# Add-OnV11.net
KiCad netlist of a schematic drawn in EAGLE
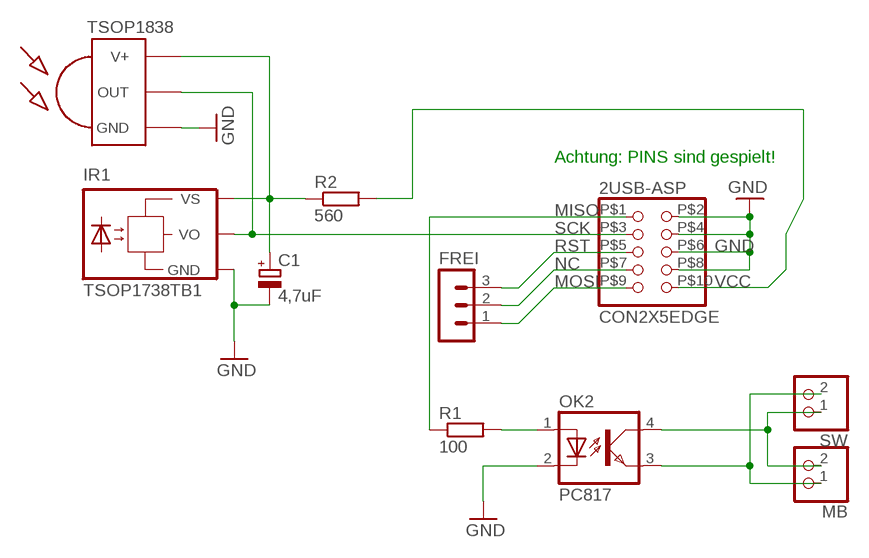
[diagram p0: schematic, sheet 1]

(export (version "E")
  (design (tool "Eeschema 10.0.6"))
  (components
    (comp (ref "2USB-ASP")
      (value "CON2X5EDGE")
      (footprint "eagle-import:CON2X5EDGE")
      (libsource (lib "eagle-import") (part "CON2X5EDGE"))
    )
    (comp (ref "C1")
      (value "4,7uF")
      (footprint "eagle-import:E1,8-4")
      (libsource (lib "eagle-import") (part "CPOL-EUE1.8-4"))
    )
    (comp (ref "FREI")
      (value "MA03-1")
      (footprint "eagle-import:MA03-1")
      (libsource (lib "eagle-import") (part "MA03-1"))
    )
    (comp (ref "IR1")
      (value "TSOP1738TB1")
      (footprint "eagle-import:TSOP17_TB1")
      (libsource (lib "eagle-import") (part "TSOP17TB138"))
    )
    (comp (ref "MB")
      (value "PINHD-1X2")
      (footprint "eagle-import:1X02")
      (libsource (lib "eagle-import") (part "PINHD-1X2"))
    )
    (comp (ref "OK2")
      (value "PC817")
      (footprint "eagle-import:DIL04")
      (fields (field (name "MPN") "PC817X4J000F"))
      (libsource (lib "eagle-import") (part "PC817"))
    )
    (comp (ref "R1")
      (value "100")
      (footprint "eagle-import:0204V")
      (libsource (lib "eagle-import") (part "R-EU_0204/2V"))
    )
    (comp (ref "R2")
      (value "560")
      (footprint "eagle-import:0204V")
      (libsource (lib "eagle-import") (part "R-EU_0204/2V"))
    )
    (comp (ref "SW")
      (value "PINHD-1X2")
      (footprint "eagle-import:1X02")
      (libsource (lib "eagle-import") (part "PINHD-1X2"))
    )
    (comp (ref "U$1")
      (value "TSOP1838")
      (footprint "eagle-import:TSOP18XX")
      (libsource (lib "eagle-import") (part "TSOP1838"))
    )
  )
  (nets
    (net (code "1") (name "/MISO") (class "Default")
      (node (ref "2USB-ASP") (pin "P$1") (pinfunction "1_P$1") (pintype "passive"))
      (node (ref "R1") (pin "1") (pinfunction "1_1") (pintype "passive"))
    )
    (net (code "2") (name "/MOSI") (class "Default")
      (node (ref "2USB-ASP") (pin "P$9") (pinfunction "9_P$9") (pintype "passive"))
      (node (ref "FREI") (pin "1") (pinfunction "1_1") (pintype "passive"))
    )
    (net (code "3") (name "/NC") (class "Default")
      (node (ref "2USB-ASP") (pin "P$7") (pinfunction "7_P$7") (pintype "passive"))
      (node (ref "FREI") (pin "2") (pinfunction "2_2") (pintype "passive"))
    )
    (net (code "4") (name "/RST") (class "Default")
      (node (ref "2USB-ASP") (pin "P$5") (pinfunction "5_P$5") (pintype "passive"))
      (node (ref "FREI") (pin "3") (pinfunction "3_3") (pintype "passive"))
    )
    (net (code "5") (name "/SCK") (class "Default")
      (node (ref "2USB-ASP") (pin "P$3") (pinfunction "3_P$3") (pintype "passive"))
      (node (ref "IR1") (pin "VO") (pinfunction "VO_VO") (pintype "open_collector"))
      (node (ref "U$1") (pin "OUT") (pinfunction "OUT_OUT") (pintype "bidirectional"))
    )
    (net (code "6") (name "/VCC") (class "Default")
      (node (ref "2USB-ASP") (pin "P$10") (pinfunction "10_P$10") (pintype "passive"))
      (node (ref "R2") (pin "2") (pinfunction "2_2") (pintype "passive"))
    )
    (net (code "7") (name "GND") (class "Default")
      (node (ref "2USB-ASP") (pin "P$2") (pinfunction "2_P$2") (pintype "passive"))
      (node (ref "2USB-ASP") (pin "P$4") (pinfunction "4_P$4") (pintype "passive"))
      (node (ref "2USB-ASP") (pin "P$6") (pinfunction "6_P$6") (pintype "passive"))
      (node (ref "2USB-ASP") (pin "P$8") (pinfunction "8_P$8") (pintype "passive"))
      (node (ref "C1") (pin "-") (pinfunction "-_-") (pintype "passive"))
      (node (ref "IR1") (pin "GND") (pinfunction "GND_GND") (pintype "power_in"))
      (node (ref "OK2") (pin "2") (pinfunction "C_2") (pintype "passive"))
      (node (ref "U$1") (pin "GND") (pinfunction "GND_GND") (pintype "bidirectional"))
    )
    (net (code "8") (name "Net-(OK2-A)") (class "Default")
      (node (ref "OK2") (pin "1") (pinfunction "A_1") (pintype "passive"))
      (node (ref "R1") (pin "2") (pinfunction "2_2") (pintype "passive"))
    )
    (net (code "9") (name "Net-(OK2-COL)") (class "Default")
      (node (ref "MB") (pin "2") (pinfunction "2_2") (pintype "passive"))
      (node (ref "OK2") (pin "4") (pinfunction "COL_4") (pintype "passive"))
      (node (ref "SW") (pin "1") (pinfunction "1_1") (pintype "passive"))
    )
    (net (code "10") (name "Net-(OK2-EMIT)") (class "Default")
      (node (ref "MB") (pin "1") (pinfunction "1_1") (pintype "passive"))
      (node (ref "OK2") (pin "3") (pinfunction "EMIT_3") (pintype "passive"))
      (node (ref "SW") (pin "2") (pinfunction "2_2") (pintype "passive"))
    )
    (net (code "11") (name "Net-(U$1-V+)") (class "Default")
      (node (ref "C1") (pin "+") (pinfunction "+_+") (pintype "passive"))
      (node (ref "IR1") (pin "VS") (pinfunction "VS_VS") (pintype "power_in"))
      (node (ref "R2") (pin "1") (pinfunction "1_1") (pintype "passive"))
      (node (ref "U$1") (pin "VCC") (pinfunction "V+_VCC") (pintype "bidirectional"))
    )
  )
)
